# lattice-isp.net
KiCad netlist of a schematic drawn in EAGLE
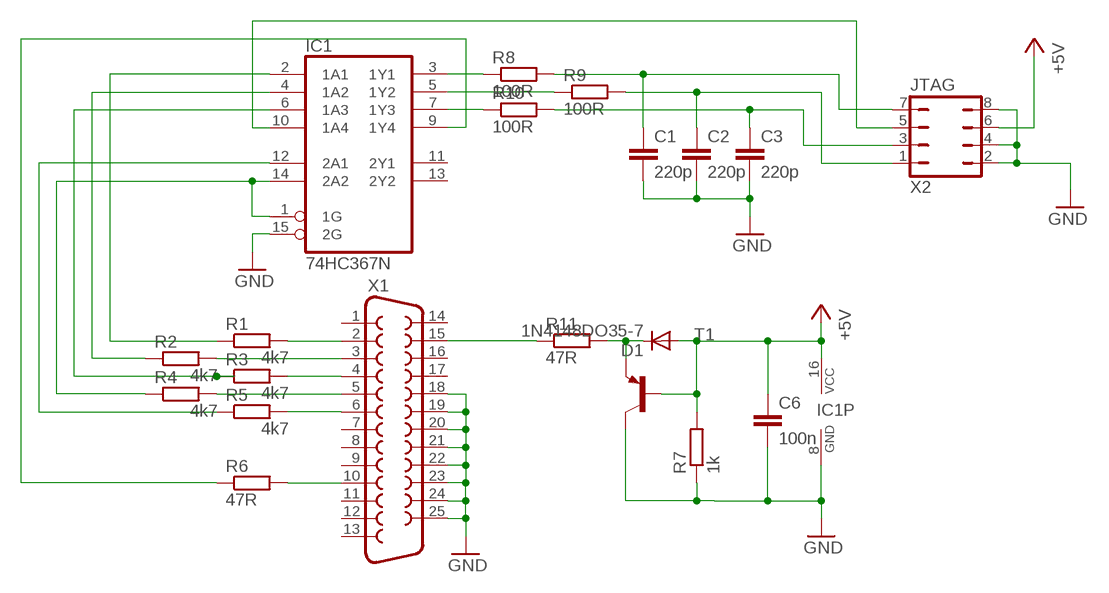
[diagram p0: schematic, sheet 1]

(export (version "E")
  (design (tool "Eeschema 10.0.6"))
  (components
    (comp (ref "C1")
      (value "220p")
      (footprint "eagle-import:C025-024X044")
      (libsource (lib "eagle-import") (part "C-EU025-024X044"))
    )
    (comp (ref "C2")
      (value "220p")
      (footprint "eagle-import:C025-024X044")
      (libsource (lib "eagle-import") (part "C-EU025-024X044"))
    )
    (comp (ref "C3")
      (value "220p")
      (footprint "eagle-import:C025-024X044")
      (libsource (lib "eagle-import") (part "C-EU025-024X044"))
    )
    (comp (ref "C6")
      (value "100n")
      (footprint "eagle-import:C050-024X044")
      (libsource (lib "eagle-import") (part "C-EU050-024X044"))
    )
    (comp (ref "D1")
      (value "1N4148DO35-7")
      (footprint "eagle-import:DO35-7")
      (libsource (lib "eagle-import") (part "1N4148DO35-7"))
    )
    (comp (ref "IC1")
      (value "74HC367N")
      (footprint "eagle-import:DIL16")
      (libsource (lib "eagle-import") (part "74367NHC"))
    )
    (comp (ref "R1")
      (value "4k7")
      (footprint "eagle-import:0207_10")
      (libsource (lib "eagle-import") (part "R-EU_0207/10"))
    )
    (comp (ref "R2")
      (value "4k7")
      (footprint "eagle-import:0207_10")
      (libsource (lib "eagle-import") (part "R-EU_0207/10"))
    )
    (comp (ref "R3")
      (value "4k7")
      (footprint "eagle-import:0207_10")
      (libsource (lib "eagle-import") (part "R-EU_0207/10"))
    )
    (comp (ref "R4")
      (value "4k7")
      (footprint "eagle-import:0207_10")
      (libsource (lib "eagle-import") (part "R-EU_0207/10"))
    )
    (comp (ref "R5")
      (value "4k7")
      (footprint "eagle-import:0207_10")
      (libsource (lib "eagle-import") (part "R-EU_0207/10"))
    )
    (comp (ref "R6")
      (value "47R")
      (footprint "eagle-import:0207_10")
      (libsource (lib "eagle-import") (part "R-EU_0207/10"))
    )
    (comp (ref "R7")
      (value "1k")
      (footprint "eagle-import:0207_10")
      (libsource (lib "eagle-import") (part "R-EU_0207/10"))
    )
    (comp (ref "R8")
      (value "100R")
      (footprint "eagle-import:0207_10")
      (libsource (lib "eagle-import") (part "R-EU_0207/10"))
    )
    (comp (ref "R9")
      (value "100R")
      (footprint "eagle-import:0207_10")
      (libsource (lib "eagle-import") (part "R-EU_0207/10"))
    )
    (comp (ref "R10")
      (value "100R")
      (footprint "eagle-import:0207_10")
      (libsource (lib "eagle-import") (part "R-EU_0207/10"))
    )
    (comp (ref "R11")
      (value "47R")
      (footprint "eagle-import:0207_10")
      (libsource (lib "eagle-import") (part "R-EU_0207/10"))
    )
    (comp (ref "T1")
      (value "BC636-PNP-TO92-BCE")
      (footprint "eagle-import:TO92-BCE")
      (libsource (lib "eagle-import") (part "-PNP-TO92-BCEBC636"))
    )
    (comp (ref "X1")
      (value "F25HP")
      (footprint "eagle-import:F25HP")
      (libsource (lib "eagle-import") (part "F25HP"))
    )
    (comp (ref "X2")
      (value "JTAG")
      (footprint "eagle-import:JP4Q")
      (libsource (lib "eagle-import") (part "JP4Q"))
    )
  )
  (nets
    (net (code "1") (name "+5V") (class "Default")
      (node (ref "C6") (pin "1") (pinfunction "1_1") (pintype "passive"))
      (node (ref "D1") (pin "A") (pinfunction "A_A") (pintype "passive"))
      (node (ref "IC1") (pin "16") (pinfunction "VCC_16") (pintype "power_in"))
      (node (ref "R7") (pin "2") (pinfunction "2_2") (pintype "passive"))
      (node (ref "T1") (pin "B") (pinfunction "B_B") (pintype "passive"))
      (node (ref "X2") (pin "6") (pinfunction "6_6") (pintype "passive"))
    )
    (net (code "2") (name "GND") (class "Default")
      (node (ref "C1") (pin "2") (pinfunction "2_2") (pintype "passive"))
      (node (ref "C2") (pin "2") (pinfunction "2_2") (pintype "passive"))
      (node (ref "C3") (pin "2") (pinfunction "2_2") (pintype "passive"))
      (node (ref "C6") (pin "2") (pinfunction "2_2") (pintype "passive"))
      (node (ref "IC1") (pin "15") (pinfunction "2G_15") (pintype "input"))
      (node (ref "IC1") (pin "8") (pinfunction "GND_8") (pintype "power_in"))
      (node (ref "R7") (pin "1") (pinfunction "1_1") (pintype "passive"))
      (node (ref "T1") (pin "C") (pinfunction "C_C") (pintype "passive"))
      (node (ref "X1") (pin "18") (pinfunction "18_18") (pintype "passive"))
      (node (ref "X1") (pin "19") (pinfunction "19_19") (pintype "passive"))
      (node (ref "X1") (pin "20") (pinfunction "20_20") (pintype "passive"))
      (node (ref "X1") (pin "21") (pinfunction "21_21") (pintype "passive"))
      (node (ref "X1") (pin "22") (pinfunction "22_22") (pintype "passive"))
      (node (ref "X1") (pin "23") (pinfunction "23_23") (pintype "passive"))
      (node (ref "X1") (pin "24") (pinfunction "24_24") (pintype "passive"))
      (node (ref "X1") (pin "25") (pinfunction "25_25") (pintype "passive"))
      (node (ref "X2") (pin "2") (pinfunction "2_2") (pintype "passive"))
      (node (ref "X2") (pin "4") (pinfunction "4_4") (pintype "passive"))
      (node (ref "X2") (pin "8") (pinfunction "8_8") (pintype "passive"))
    )
    (net (code "3") (name "Net-(C1-Pad1)") (class "Default")
      (node (ref "C1") (pin "1") (pinfunction "1_1") (pintype "passive"))
      (node (ref "R8") (pin "2") (pinfunction "2_2") (pintype "passive"))
      (node (ref "X2") (pin "7") (pinfunction "7_7") (pintype "passive"))
    )
    (net (code "4") (name "Net-(C2-Pad1)") (class "Default")
      (node (ref "C2") (pin "1") (pinfunction "1_1") (pintype "passive"))
      (node (ref "R9") (pin "2") (pinfunction "2_2") (pintype "passive"))
      (node (ref "X2") (pin "1") (pinfunction "1_1") (pintype "passive"))
    )
    (net (code "5") (name "Net-(C3-Pad1)") (class "Default")
      (node (ref "C3") (pin "1") (pinfunction "1_1") (pintype "passive"))
      (node (ref "R10") (pin "2") (pinfunction "2_2") (pintype "passive"))
      (node (ref "X2") (pin "3") (pinfunction "3_3") (pintype "passive"))
    )
    (net (code "6") (name "Net-(D1-PadC)") (class "Default")
      (node (ref "D1") (pin "C") (pinfunction "C_C") (pintype "passive"))
      (node (ref "R11") (pin "2") (pinfunction "2_2") (pintype "passive"))
      (node (ref "T1") (pin "E") (pinfunction "E_E") (pintype "passive"))
    )
    (net (code "7") (name "Net-(IC1A-1A1)") (class "Default")
      (node (ref "IC1") (pin "2") (pinfunction "1A1_2") (pintype "input"))
      (node (ref "R1") (pin "1") (pinfunction "1_1") (pintype "passive"))
    )
    (net (code "8") (name "Net-(IC1A-1A2)") (class "Default")
      (node (ref "IC1") (pin "4") (pinfunction "1A2_4") (pintype "input"))
      (node (ref "R2") (pin "1") (pinfunction "1_1") (pintype "passive"))
    )
    (net (code "9") (name "Net-(IC1A-1A3)") (class "Default")
      (node (ref "IC1") (pin "6") (pinfunction "1A3_6") (pintype "input"))
      (node (ref "R3") (pin "1") (pinfunction "1_1") (pintype "passive"))
    )
    (net (code "10") (name "Net-(IC1A-1A4)") (class "Default")
      (node (ref "IC1") (pin "10") (pinfunction "1A4_10") (pintype "input"))
      (node (ref "X2") (pin "5") (pinfunction "5_5") (pintype "passive"))
    )
    (net (code "11") (name "Net-(IC1A-1G)") (class "Default")
      (node (ref "IC1") (pin "1") (pinfunction "1G_1") (pintype "input"))
      (node (ref "IC1") (pin "14") (pinfunction "2A2_14") (pintype "input"))
      (node (ref "R4") (pin "1") (pinfunction "1_1") (pintype "passive"))
    )
    (net (code "12") (name "Net-(IC1A-1Y1)") (class "Default")
      (node (ref "IC1") (pin "3") (pinfunction "1Y1_3") (pintype "tri_state"))
      (node (ref "R8") (pin "1") (pinfunction "1_1") (pintype "passive"))
    )
    (net (code "13") (name "Net-(IC1A-1Y2)") (class "Default")
      (node (ref "IC1") (pin "5") (pinfunction "1Y2_5") (pintype "tri_state"))
      (node (ref "R9") (pin "1") (pinfunction "1_1") (pintype "passive"))
    )
    (net (code "14") (name "Net-(IC1A-1Y3)") (class "Default")
      (node (ref "IC1") (pin "7") (pinfunction "1Y3_7") (pintype "tri_state"))
      (node (ref "R10") (pin "1") (pinfunction "1_1") (pintype "passive"))
    )
    (net (code "15") (name "Net-(IC1A-1Y4)") (class "Default")
      (node (ref "IC1") (pin "9") (pinfunction "1Y4_9") (pintype "tri_state"))
      (node (ref "R6") (pin "1") (pinfunction "1_1") (pintype "passive"))
    )
    (net (code "16") (name "Net-(IC1A-2A1)") (class "Default")
      (node (ref "IC1") (pin "12") (pinfunction "2A1_12") (pintype "input"))
      (node (ref "R5") (pin "1") (pinfunction "1_1") (pintype "passive"))
    )
    (net (code "17") (name "Net-(R1-Pad2)") (class "Default")
      (node (ref "R1") (pin "2") (pinfunction "2_2") (pintype "passive"))
      (node (ref "X1") (pin "2") (pinfunction "2_2") (pintype "passive"))
    )
    (net (code "18") (name "Net-(R2-Pad2)") (class "Default")
      (node (ref "R2") (pin "2") (pinfunction "2_2") (pintype "passive"))
      (node (ref "X1") (pin "3") (pinfunction "3_3") (pintype "passive"))
    )
    (net (code "19") (name "Net-(R3-Pad2)") (class "Default")
      (node (ref "R3") (pin "2") (pinfunction "2_2") (pintype "passive"))
      (node (ref "X1") (pin "4") (pinfunction "4_4") (pintype "passive"))
    )
    (net (code "20") (name "Net-(R4-Pad2)") (class "Default")
      (node (ref "R4") (pin "2") (pinfunction "2_2") (pintype "passive"))
      (node (ref "X1") (pin "5") (pinfunction "5_5") (pintype "passive"))
    )
    (net (code "21") (name "Net-(R5-Pad2)") (class "Default")
      (node (ref "R5") (pin "2") (pinfunction "2_2") (pintype "passive"))
      (node (ref "X1") (pin "6") (pinfunction "6_6") (pintype "passive"))
    )
    (net (code "22") (name "Net-(R6-Pad2)") (class "Default")
      (node (ref "R6") (pin "2") (pinfunction "2_2") (pintype "passive"))
      (node (ref "X1") (pin "10") (pinfunction "10_10") (pintype "passive"))
    )
    (net (code "23") (name "Net-(R11-Pad1)") (class "Default")
      (node (ref "R11") (pin "1") (pinfunction "1_1") (pintype "passive"))
      (node (ref "X1") (pin "15") (pinfunction "15_15") (pintype "passive"))
    )
    (net (code "24") (name "unconnected-(IC1A-2Y1-Pad11)") (class "Default")
      (node (ref "IC1") (pin "11") (pinfunction "2Y1_11") (pintype "tri_state"))
    )
    (net (code "25") (name "unconnected-(IC1A-2Y2-Pad13)") (class "Default")
      (node (ref "IC1") (pin "13") (pinfunction "2Y2_13") (pintype "tri_state"))
    )
    (net (code "26") (name "unconnected-(X1-Pad1)") (class "Default")
      (node (ref "X1") (pin "1") (pinfunction "1_1") (pintype "passive"))
    )
    (net (code "27") (name "unconnected-(X1-Pad7)") (class "Default")
      (node (ref "X1") (pin "7") (pinfunction "7_7") (pintype "passive"))
    )
    (net (code "28") (name "unconnected-(X1-Pad8)") (class "Default")
      (node (ref "X1") (pin "8") (pinfunction "8_8") (pintype "passive"))
    )
    (net (code "29") (name "unconnected-(X1-Pad9)") (class "Default")
      (node (ref "X1") (pin "9") (pinfunction "9_9") (pintype "passive"))
    )
    (net (code "30") (name "unconnected-(X1-Pad11)") (class "Default")
      (node (ref "X1") (pin "11") (pinfunction "11_11") (pintype "passive"))
    )
    (net (code "31") (name "unconnected-(X1-Pad12)") (class "Default")
      (node (ref "X1") (pin "12") (pinfunction "12_12") (pintype "passive"))
    )
    (net (code "32") (name "unconnected-(X1-Pad13)") (class "Default")
      (node (ref "X1") (pin "13") (pinfunction "13_13") (pintype "passive"))
    )
    (net (code "33") (name "unconnected-(X1-Pad14)") (class "Default")
      (node (ref "X1") (pin "14") (pinfunction "14_14") (pintype "passive"))
    )
    (net (code "34") (name "unconnected-(X1-Pad16)") (class "Default")
      (node (ref "X1") (pin "16") (pinfunction "16_16") (pintype "passive"))
    )
    (net (code "35") (name "unconnected-(X1-Pad17)") (class "Default")
      (node (ref "X1") (pin "17") (pinfunction "17_17") (pintype "passive"))
    )
  )
)
